# Large_Digit_Driver.net
KiCad netlist of a schematic drawn in EAGLE
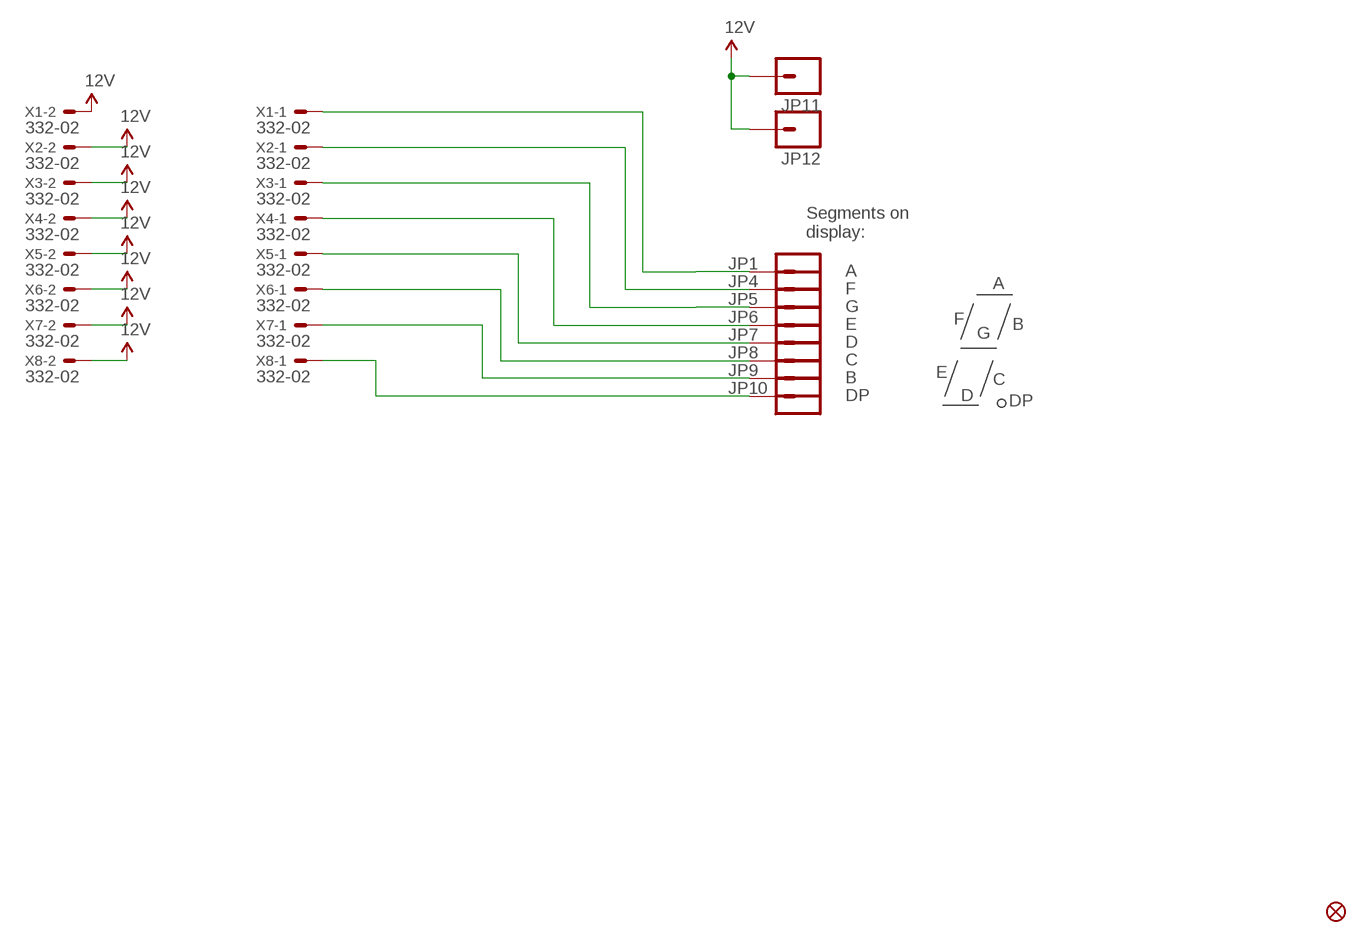
[diagram p0: schematic, sheet 1]

(export (version "E")
  (design (tool "Eeschema 10.0.6"))
  (components
    (comp (ref "FID2")
      (value "FIDUCIAL1X2")
      (footprint "eagle-import:FIDUCIAL-1X2")
      (libsource (lib "eagle-import") (part "FIDUCIAL1X2"))
    )
    (comp (ref "JP1")
      (value "M01PTH_LONGPAD")
      (footprint "eagle-import:1X01_LONGPAD")
      (libsource (lib "eagle-import") (part "M01PTH_LONGPAD"))
    )
    (comp (ref "JP4")
      (value "M01PTH_LONGPAD")
      (footprint "eagle-import:1X01_LONGPAD")
      (libsource (lib "eagle-import") (part "M01PTH_LONGPAD"))
    )
    (comp (ref "JP5")
      (value "M01PTH_LONGPAD")
      (footprint "eagle-import:1X01_LONGPAD")
      (libsource (lib "eagle-import") (part "M01PTH_LONGPAD"))
    )
    (comp (ref "JP6")
      (value "M01PTH_LONGPAD")
      (footprint "eagle-import:1X01_LONGPAD")
      (libsource (lib "eagle-import") (part "M01PTH_LONGPAD"))
    )
    (comp (ref "JP7")
      (value "M01PTH_LONGPAD")
      (footprint "eagle-import:1X01_LONGPAD")
      (libsource (lib "eagle-import") (part "M01PTH_LONGPAD"))
    )
    (comp (ref "JP8")
      (value "M01PTH_LONGPAD")
      (footprint "eagle-import:1X01_LONGPAD")
      (libsource (lib "eagle-import") (part "M01PTH_LONGPAD"))
    )
    (comp (ref "JP9")
      (value "M01PTH_LONGPAD")
      (footprint "eagle-import:1X01_LONGPAD")
      (libsource (lib "eagle-import") (part "M01PTH_LONGPAD"))
    )
    (comp (ref "JP10")
      (value "M01PTH_LONGPAD")
      (footprint "eagle-import:1X01_LONGPAD")
      (libsource (lib "eagle-import") (part "M01PTH_LONGPAD"))
    )
    (comp (ref "JP11")
      (value "M01PTH_LONGPAD")
      (footprint "eagle-import:1X01_LONGPAD")
      (libsource (lib "eagle-import") (part "M01PTH_LONGPAD"))
    )
    (comp (ref "JP12")
      (value "M01PTH_LONGPAD")
      (footprint "eagle-import:1X01_LONGPAD")
      (libsource (lib "eagle-import") (part "M01PTH_LONGPAD"))
    )
    (comp (ref "X1")
      (value "332-02")
      (footprint "eagle-import:332-02")
      (libsource (lib "eagle-import") (part "332-02"))
    )
    (comp (ref "X2")
      (value "332-02")
      (footprint "eagle-import:332-02")
      (libsource (lib "eagle-import") (part "332-02"))
    )
    (comp (ref "X3")
      (value "332-02")
      (footprint "eagle-import:332-02")
      (libsource (lib "eagle-import") (part "332-02"))
    )
    (comp (ref "X4")
      (value "332-02")
      (footprint "eagle-import:332-02")
      (libsource (lib "eagle-import") (part "332-02"))
    )
    (comp (ref "X5")
      (value "332-02")
      (footprint "eagle-import:332-02")
      (libsource (lib "eagle-import") (part "332-02"))
    )
    (comp (ref "X6")
      (value "332-02")
      (footprint "eagle-import:332-02")
      (libsource (lib "eagle-import") (part "332-02"))
    )
    (comp (ref "X7")
      (value "332-02")
      (footprint "eagle-import:332-02")
      (libsource (lib "eagle-import") (part "332-02"))
    )
    (comp (ref "X8")
      (value "332-02")
      (footprint "eagle-import:332-02")
      (libsource (lib "eagle-import") (part "332-02"))
    )
  )
  (nets
    (net (code "1") (name "12V") (class "Default")
      (node (ref "JP11") (pin "1") (pinfunction "1_1") (pintype "passive"))
      (node (ref "JP12") (pin "1") (pinfunction "1_1") (pintype "passive"))
      (node (ref "X1") (pin "2") (pinfunction "S_2") (pintype "passive"))
      (node (ref "X2") (pin "2") (pinfunction "S_2") (pintype "passive"))
      (node (ref "X3") (pin "2") (pinfunction "S_2") (pintype "passive"))
      (node (ref "X4") (pin "2") (pinfunction "S_2") (pintype "passive"))
      (node (ref "X5") (pin "2") (pinfunction "S_2") (pintype "passive"))
      (node (ref "X6") (pin "2") (pinfunction "S_2") (pintype "passive"))
      (node (ref "X7") (pin "2") (pinfunction "S_2") (pintype "passive"))
      (node (ref "X8") (pin "2") (pinfunction "S_2") (pintype "passive"))
    )
    (net (code "2") (name "Net-(X1A-S)") (class "Default")
      (node (ref "JP1") (pin "1") (pinfunction "1_1") (pintype "passive"))
      (node (ref "X1") (pin "1") (pinfunction "S_1") (pintype "passive"))
    )
    (net (code "3") (name "Net-(X2A-S)") (class "Default")
      (node (ref "JP4") (pin "1") (pinfunction "1_1") (pintype "passive"))
      (node (ref "X2") (pin "1") (pinfunction "S_1") (pintype "passive"))
    )
    (net (code "4") (name "Net-(X3A-S)") (class "Default")
      (node (ref "JP5") (pin "1") (pinfunction "1_1") (pintype "passive"))
      (node (ref "X3") (pin "1") (pinfunction "S_1") (pintype "passive"))
    )
    (net (code "5") (name "Net-(X4A-S)") (class "Default")
      (node (ref "JP6") (pin "1") (pinfunction "1_1") (pintype "passive"))
      (node (ref "X4") (pin "1") (pinfunction "S_1") (pintype "passive"))
    )
    (net (code "6") (name "Net-(X5A-S)") (class "Default")
      (node (ref "JP7") (pin "1") (pinfunction "1_1") (pintype "passive"))
      (node (ref "X5") (pin "1") (pinfunction "S_1") (pintype "passive"))
    )
    (net (code "7") (name "Net-(X6A-S)") (class "Default")
      (node (ref "JP8") (pin "1") (pinfunction "1_1") (pintype "passive"))
      (node (ref "X6") (pin "1") (pinfunction "S_1") (pintype "passive"))
    )
    (net (code "8") (name "Net-(X7A-S)") (class "Default")
      (node (ref "JP9") (pin "1") (pinfunction "1_1") (pintype "passive"))
      (node (ref "X7") (pin "1") (pinfunction "S_1") (pintype "passive"))
    )
    (net (code "9") (name "Net-(X8A-S)") (class "Default")
      (node (ref "JP10") (pin "1") (pinfunction "1_1") (pintype "passive"))
      (node (ref "X8") (pin "1") (pinfunction "S_1") (pintype "passive"))
    )
  )
)
